# ProtoBoard.net
KiCad netlist of a schematic drawn in EAGLE
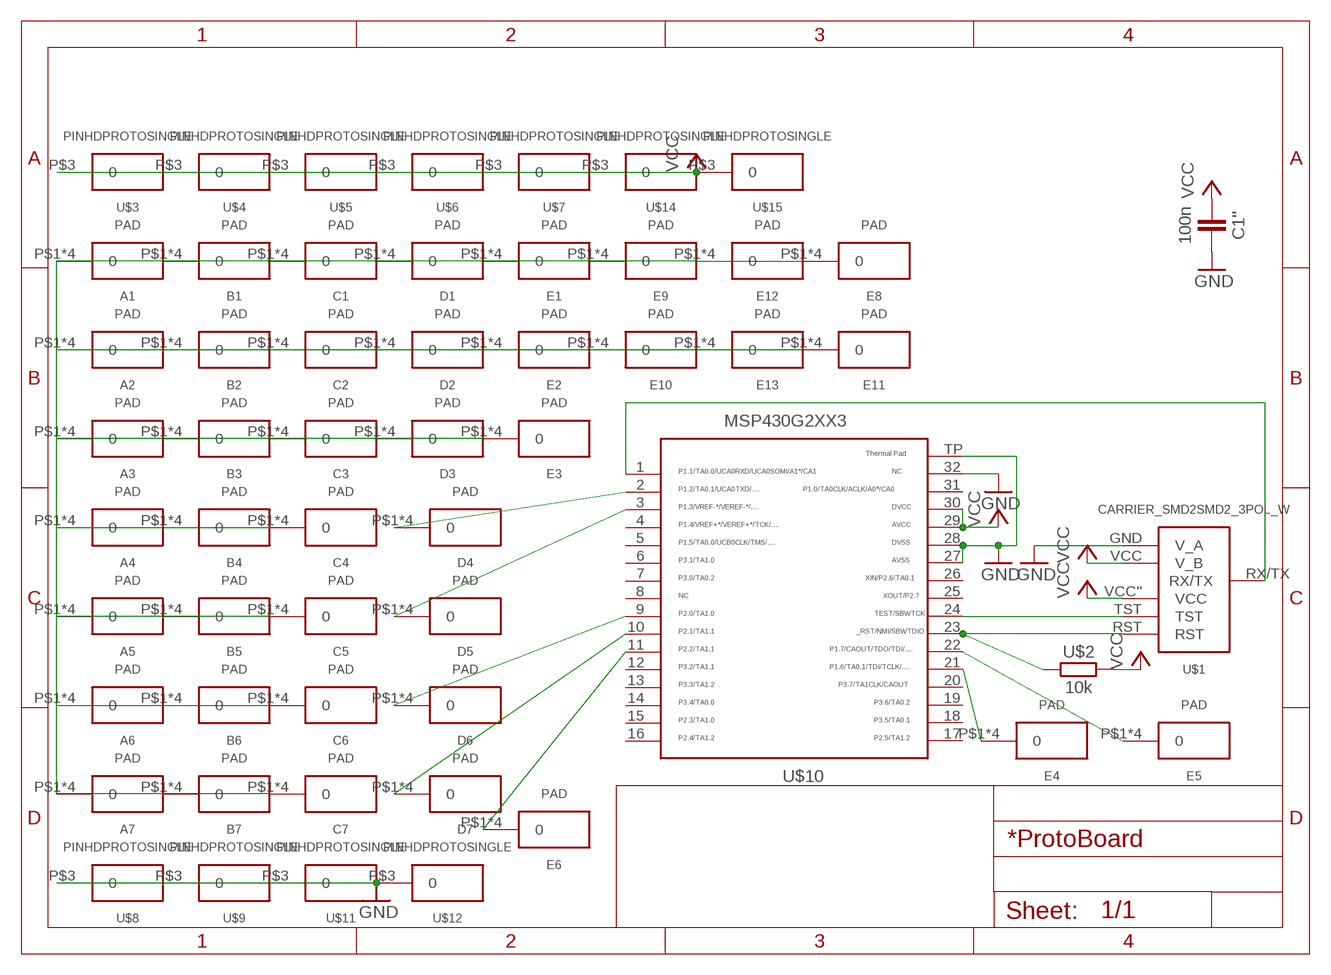
[diagram p0: schematic, sheet 1]

(export (version "E")
  (design (tool "Eeschema 10.0.6"))
  (components
    (comp (ref "A1")
      (value "PAD")
      (footprint "eagle-import:PROTPAD")
      (libsource (lib "eagle-import") (part "PINHDPROTOTYPING"))
    )
    (comp (ref "A2")
      (value "PAD")
      (footprint "eagle-import:PROTPAD")
      (libsource (lib "eagle-import") (part "PINHDPROTOTYPING"))
    )
    (comp (ref "A3")
      (value "PAD")
      (footprint "eagle-import:PROTPAD")
      (libsource (lib "eagle-import") (part "PINHDPROTOTYPING"))
    )
    (comp (ref "A4")
      (value "PAD")
      (footprint "eagle-import:PROTPAD")
      (libsource (lib "eagle-import") (part "PINHDPROTOTYPING"))
    )
    (comp (ref "A5")
      (value "PAD")
      (footprint "eagle-import:PROTPAD")
      (libsource (lib "eagle-import") (part "PINHDPROTOTYPING"))
    )
    (comp (ref "A6")
      (value "PAD")
      (footprint "eagle-import:PROTPAD")
      (libsource (lib "eagle-import") (part "PINHDPROTOTYPING"))
    )
    (comp (ref "A7")
      (value "PAD")
      (footprint "eagle-import:PROTPAD")
      (libsource (lib "eagle-import") (part "PINHDPROTOTYPING"))
    )
    (comp (ref "B1")
      (value "PAD")
      (footprint "eagle-import:PROTPAD")
      (libsource (lib "eagle-import") (part "PINHDPROTOTYPING"))
    )
    (comp (ref "B2")
      (value "PAD")
      (footprint "eagle-import:PROTPAD")
      (libsource (lib "eagle-import") (part "PINHDPROTOTYPING"))
    )
    (comp (ref "B3")
      (value "PAD")
      (footprint "eagle-import:PROTPAD")
      (libsource (lib "eagle-import") (part "PINHDPROTOTYPING"))
    )
    (comp (ref "B4")
      (value "PAD")
      (footprint "eagle-import:PROTPAD")
      (libsource (lib "eagle-import") (part "PINHDPROTOTYPING"))
    )
    (comp (ref "B5")
      (value "PAD")
      (footprint "eagle-import:PROTPAD")
      (libsource (lib "eagle-import") (part "PINHDPROTOTYPING"))
    )
    (comp (ref "B6")
      (value "PAD")
      (footprint "eagle-import:PROTPAD")
      (libsource (lib "eagle-import") (part "PINHDPROTOTYPING"))
    )
    (comp (ref "B7")
      (value "PAD")
      (footprint "eagle-import:PROTPAD")
      (libsource (lib "eagle-import") (part "PINHDPROTOTYPING"))
    )
    (comp (ref "C1")
      (value "PAD")
      (footprint "eagle-import:PROTPAD")
      (libsource (lib "eagle-import") (part "PINHDPROTOTYPING"))
    )
    (comp (ref "C1''")
      (value "100n")
      (footprint "eagle-import:603")
      (libsource (lib "eagle-import") (part "CAPACITOR"))
    )
    (comp (ref "C2")
      (value "PAD")
      (footprint "eagle-import:PROTPAD")
      (libsource (lib "eagle-import") (part "PINHDPROTOTYPING"))
    )
    (comp (ref "C3")
      (value "PAD")
      (footprint "eagle-import:PROTPAD")
      (libsource (lib "eagle-import") (part "PINHDPROTOTYPING"))
    )
    (comp (ref "C4")
      (value "PAD")
      (footprint "eagle-import:PROTPAD")
      (libsource (lib "eagle-import") (part "PINHDPROTOTYPING"))
    )
    (comp (ref "C5")
      (value "PAD")
      (footprint "eagle-import:PROTPAD")
      (libsource (lib "eagle-import") (part "PINHDPROTOTYPING"))
    )
    (comp (ref "C6")
      (value "PAD")
      (footprint "eagle-import:PROTPAD")
      (libsource (lib "eagle-import") (part "PINHDPROTOTYPING"))
    )
    (comp (ref "C7")
      (value "PAD")
      (footprint "eagle-import:PROTPAD")
      (libsource (lib "eagle-import") (part "PINHDPROTOTYPING"))
    )
    (comp (ref "D1")
      (value "PAD")
      (footprint "eagle-import:PROTPAD")
      (libsource (lib "eagle-import") (part "PINHDPROTOTYPING"))
    )
    (comp (ref "D2")
      (value "PAD")
      (footprint "eagle-import:PROTPAD")
      (libsource (lib "eagle-import") (part "PINHDPROTOTYPING"))
    )
    (comp (ref "D3")
      (value "PAD")
      (footprint "eagle-import:PROTPAD")
      (libsource (lib "eagle-import") (part "PINHDPROTOTYPING"))
    )
    (comp (ref "D4")
      (value "PAD")
      (footprint "eagle-import:PROTPAD")
      (libsource (lib "eagle-import") (part "PINHDPROTOTYPING"))
    )
    (comp (ref "D5")
      (value "PAD")
      (footprint "eagle-import:PROTPAD")
      (libsource (lib "eagle-import") (part "PINHDPROTOTYPING"))
    )
    (comp (ref "D6")
      (value "PAD")
      (footprint "eagle-import:PROTPAD")
      (libsource (lib "eagle-import") (part "PINHDPROTOTYPING"))
    )
    (comp (ref "D7")
      (value "PAD")
      (footprint "eagle-import:PROTPAD")
      (libsource (lib "eagle-import") (part "PINHDPROTOTYPING"))
    )
    (comp (ref "E1")
      (value "PAD")
      (footprint "eagle-import:PROTPAD")
      (libsource (lib "eagle-import") (part "PINHDPROTOTYPING"))
    )
    (comp (ref "E2")
      (value "PAD")
      (footprint "eagle-import:PROTPAD")
      (libsource (lib "eagle-import") (part "PINHDPROTOTYPING"))
    )
    (comp (ref "E3")
      (value "PAD")
      (footprint "eagle-import:PROTPAD")
      (libsource (lib "eagle-import") (part "PINHDPROTOTYPING"))
    )
    (comp (ref "E4")
      (value "PAD")
      (footprint "eagle-import:PROTPAD")
      (libsource (lib "eagle-import") (part "PINHDPROTOTYPING"))
    )
    (comp (ref "E5")
      (value "PAD")
      (footprint "eagle-import:PROTPAD")
      (libsource (lib "eagle-import") (part "PINHDPROTOTYPING"))
    )
    (comp (ref "E6")
      (value "PAD")
      (footprint "eagle-import:PROTPAD")
      (libsource (lib "eagle-import") (part "PINHDPROTOTYPING"))
    )
    (comp (ref "E8")
      (value "PAD")
      (footprint "eagle-import:PROTPAD")
      (libsource (lib "eagle-import") (part "PINHDPROTOTYPING"))
    )
    (comp (ref "E9")
      (value "PAD")
      (footprint "eagle-import:PROTPAD")
      (libsource (lib "eagle-import") (part "PINHDPROTOTYPING"))
    )
    (comp (ref "E10")
      (value "PAD")
      (footprint "eagle-import:PROTPAD")
      (libsource (lib "eagle-import") (part "PINHDPROTOTYPING"))
    )
    (comp (ref "E11")
      (value "PAD")
      (footprint "eagle-import:PROTPAD")
      (libsource (lib "eagle-import") (part "PINHDPROTOTYPING"))
    )
    (comp (ref "E12")
      (value "PAD")
      (footprint "eagle-import:PROTPAD")
      (libsource (lib "eagle-import") (part "PINHDPROTOTYPING"))
    )
    (comp (ref "E13")
      (value "PAD")
      (footprint "eagle-import:PROTPAD")
      (libsource (lib "eagle-import") (part "PINHDPROTOTYPING"))
    )
    (comp (ref "U$1")
      (value "CARRIER_SMD2SMD2_3POL_W")
      (footprint "eagle-import:CARRIER_SMD2_WIDE_3POL")
      (libsource (lib "eagle-import") (part "CARRIER_SMD2SMD2_3POL_W"))
    )
    (comp (ref "U$2")
      (value "10k")
      (footprint "eagle-import:603")
      (libsource (lib "eagle-import") (part "RESISTOR0603"))
    )
    (comp (ref "U$3")
      (value "PINHDPROTOSINGLE")
      (footprint "eagle-import:PROTOPADSINGLE")
      (libsource (lib "eagle-import") (part "PINHDPROTOSINGLE"))
    )
    (comp (ref "U$4")
      (value "PINHDPROTOSINGLE")
      (footprint "eagle-import:PROTOPADSINGLE")
      (libsource (lib "eagle-import") (part "PINHDPROTOSINGLE"))
    )
    (comp (ref "U$5")
      (value "PINHDPROTOSINGLE")
      (footprint "eagle-import:PROTOPADSINGLE")
      (libsource (lib "eagle-import") (part "PINHDPROTOSINGLE"))
    )
    (comp (ref "U$6")
      (value "PINHDPROTOSINGLE")
      (footprint "eagle-import:PROTOPADSINGLE")
      (libsource (lib "eagle-import") (part "PINHDPROTOSINGLE"))
    )
    (comp (ref "U$7")
      (value "PINHDPROTOSINGLE")
      (footprint "eagle-import:PROTOPADSINGLE")
      (libsource (lib "eagle-import") (part "PINHDPROTOSINGLE"))
    )
    (comp (ref "U$8")
      (value "PINHDPROTOSINGLE")
      (footprint "eagle-import:PROTOPADSINGLE")
      (libsource (lib "eagle-import") (part "PINHDPROTOSINGLE"))
    )
    (comp (ref "U$9")
      (value "PINHDPROTOSINGLE")
      (footprint "eagle-import:PROTOPADSINGLE")
      (libsource (lib "eagle-import") (part "PINHDPROTOSINGLE"))
    )
    (comp (ref "U$10")
      (value "MSP430G2553")
      (footprint "eagle-import:QFN32")
      (libsource (lib "eagle-import") (part "MSP430G2553"))
    )
    (comp (ref "U$11")
      (value "PINHDPROTOSINGLE")
      (footprint "eagle-import:PROTOPADSINGLE")
      (libsource (lib "eagle-import") (part "PINHDPROTOSINGLE"))
    )
    (comp (ref "U$12")
      (value "PINHDPROTOSINGLE")
      (footprint "eagle-import:PROTOPADSINGLE")
      (libsource (lib "eagle-import") (part "PINHDPROTOSINGLE"))
    )
    (comp (ref "U$14")
      (value "PINHDPROTOSINGLE")
      (footprint "eagle-import:PROTOPADSINGLE")
      (libsource (lib "eagle-import") (part "PINHDPROTOSINGLE"))
    )
    (comp (ref "U$15")
      (value "PINHDPROTOSINGLE")
      (footprint "eagle-import:PROTOPADSINGLE")
      (libsource (lib "eagle-import") (part "PINHDPROTOSINGLE"))
    )
  )
  (nets
    (net (code "1") (name "GND") (class "Default")
      (node (ref "C1''") (pin "2") (pinfunction "2_2") (pintype "passive"))
      (node (ref "U$1") (pin "GND") (pinfunction "V_A_GND") (pintype "bidirectional"))
      (node (ref "U$10") (pin "27") (pinfunction "27_27") (pintype "bidirectional"))
      (node (ref "U$10") (pin "28") (pinfunction "28_28") (pintype "bidirectional"))
      (node (ref "U$10") (pin "32") (pinfunction "32_32") (pintype "bidirectional"))
      (node (ref "U$10") (pin "TP") (pinfunction "TP_TP") (pintype "bidirectional"))
      (node (ref "U$11") (pin "P$3") (pinfunction "0_P$3") (pintype "bidirectional"))
      (node (ref "U$12") (pin "P$3") (pinfunction "0_P$3") (pintype "bidirectional"))
      (node (ref "U$8") (pin "P$3") (pinfunction "0_P$3") (pintype "bidirectional"))
      (node (ref "U$9") (pin "P$3") (pinfunction "0_P$3") (pintype "bidirectional"))
    )
    (net (code "2") (name "Net-(A1-0-PadP$1)") (class "Default")
      (node (ref "A1") (pin "P$1") (pinfunction "0_P$1") (pintype "bidirectional"))
      (node (ref "A1") (pin "P$2") (pinfunction "0_P$2") (pintype "bidirectional"))
      (node (ref "A1") (pin "P$3") (pinfunction "0_P$3") (pintype "bidirectional"))
      (node (ref "A1") (pin "P$4") (pinfunction "0_P$4") (pintype "bidirectional"))
      (node (ref "A2") (pin "P$1") (pinfunction "0_P$1") (pintype "bidirectional"))
      (node (ref "A2") (pin "P$2") (pinfunction "0_P$2") (pintype "bidirectional"))
      (node (ref "A2") (pin "P$3") (pinfunction "0_P$3") (pintype "bidirectional"))
      (node (ref "A2") (pin "P$4") (pinfunction "0_P$4") (pintype "bidirectional"))
      (node (ref "A3") (pin "P$1") (pinfunction "0_P$1") (pintype "bidirectional"))
      (node (ref "A3") (pin "P$2") (pinfunction "0_P$2") (pintype "bidirectional"))
      (node (ref "A3") (pin "P$3") (pinfunction "0_P$3") (pintype "bidirectional"))
      (node (ref "A3") (pin "P$4") (pinfunction "0_P$4") (pintype "bidirectional"))
      (node (ref "A4") (pin "P$1") (pinfunction "0_P$1") (pintype "bidirectional"))
      (node (ref "A4") (pin "P$2") (pinfunction "0_P$2") (pintype "bidirectional"))
      (node (ref "A4") (pin "P$3") (pinfunction "0_P$3") (pintype "bidirectional"))
      (node (ref "A4") (pin "P$4") (pinfunction "0_P$4") (pintype "bidirectional"))
      (node (ref "A5") (pin "P$1") (pinfunction "0_P$1") (pintype "bidirectional"))
      (node (ref "A5") (pin "P$2") (pinfunction "0_P$2") (pintype "bidirectional"))
      (node (ref "A5") (pin "P$3") (pinfunction "0_P$3") (pintype "bidirectional"))
      (node (ref "A5") (pin "P$4") (pinfunction "0_P$4") (pintype "bidirectional"))
      (node (ref "A6") (pin "P$1") (pinfunction "0_P$1") (pintype "bidirectional"))
      (node (ref "A6") (pin "P$2") (pinfunction "0_P$2") (pintype "bidirectional"))
      (node (ref "A6") (pin "P$3") (pinfunction "0_P$3") (pintype "bidirectional"))
      (node (ref "A6") (pin "P$4") (pinfunction "0_P$4") (pintype "bidirectional"))
      (node (ref "A7") (pin "P$1") (pinfunction "0_P$1") (pintype "bidirectional"))
      (node (ref "A7") (pin "P$2") (pinfunction "0_P$2") (pintype "bidirectional"))
      (node (ref "A7") (pin "P$3") (pinfunction "0_P$3") (pintype "bidirectional"))
      (node (ref "A7") (pin "P$4") (pinfunction "0_P$4") (pintype "bidirectional"))
      (node (ref "B1") (pin "P$1") (pinfunction "0_P$1") (pintype "bidirectional"))
      (node (ref "B1") (pin "P$2") (pinfunction "0_P$2") (pintype "bidirectional"))
      (node (ref "B1") (pin "P$3") (pinfunction "0_P$3") (pintype "bidirectional"))
      (node (ref "B1") (pin "P$4") (pinfunction "0_P$4") (pintype "bidirectional"))
      (node (ref "B2") (pin "P$1") (pinfunction "0_P$1") (pintype "bidirectional"))
      (node (ref "B2") (pin "P$2") (pinfunction "0_P$2") (pintype "bidirectional"))
      (node (ref "B2") (pin "P$3") (pinfunction "0_P$3") (pintype "bidirectional"))
      (node (ref "B2") (pin "P$4") (pinfunction "0_P$4") (pintype "bidirectional"))
      (node (ref "B3") (pin "P$1") (pinfunction "0_P$1") (pintype "bidirectional"))
      (node (ref "B3") (pin "P$2") (pinfunction "0_P$2") (pintype "bidirectional"))
      (node (ref "B3") (pin "P$3") (pinfunction "0_P$3") (pintype "bidirectional"))
      (node (ref "B3") (pin "P$4") (pinfunction "0_P$4") (pintype "bidirectional"))
      (node (ref "B4") (pin "P$1") (pinfunction "0_P$1") (pintype "bidirectional"))
      (node (ref "B4") (pin "P$2") (pinfunction "0_P$2") (pintype "bidirectional"))
      (node (ref "B4") (pin "P$3") (pinfunction "0_P$3") (pintype "bidirectional"))
      (node (ref "B4") (pin "P$4") (pinfunction "0_P$4") (pintype "bidirectional"))
      (node (ref "B5") (pin "P$1") (pinfunction "0_P$1") (pintype "bidirectional"))
      (node (ref "B5") (pin "P$2") (pinfunction "0_P$2") (pintype "bidirectional"))
      (node (ref "B5") (pin "P$3") (pinfunction "0_P$3") (pintype "bidirectional"))
      (node (ref "B5") (pin "P$4") (pinfunction "0_P$4") (pintype "bidirectional"))
      (node (ref "B6") (pin "P$1") (pinfunction "0_P$1") (pintype "bidirectional"))
      (node (ref "B6") (pin "P$2") (pinfunction "0_P$2") (pintype "bidirectional"))
      (node (ref "B6") (pin "P$3") (pinfunction "0_P$3") (pintype "bidirectional"))
      (node (ref "B6") (pin "P$4") (pinfunction "0_P$4") (pintype "bidirectional"))
      (node (ref "B7") (pin "P$1") (pinfunction "0_P$1") (pintype "bidirectional"))
      (node (ref "B7") (pin "P$2") (pinfunction "0_P$2") (pintype "bidirectional"))
      (node (ref "B7") (pin "P$3") (pinfunction "0_P$3") (pintype "bidirectional"))
      (node (ref "B7") (pin "P$4") (pinfunction "0_P$4") (pintype "bidirectional"))
      (node (ref "C1") (pin "P$1") (pinfunction "0_P$1") (pintype "bidirectional"))
      (node (ref "C1") (pin "P$2") (pinfunction "0_P$2") (pintype "bidirectional"))
      (node (ref "C1") (pin "P$3") (pinfunction "0_P$3") (pintype "bidirectional"))
      (node (ref "C1") (pin "P$4") (pinfunction "0_P$4") (pintype "bidirectional"))
      (node (ref "C2") (pin "P$1") (pinfunction "0_P$1") (pintype "bidirectional"))
      (node (ref "C2") (pin "P$2") (pinfunction "0_P$2") (pintype "bidirectional"))
      (node (ref "C2") (pin "P$3") (pinfunction "0_P$3") (pintype "bidirectional"))
      (node (ref "C2") (pin "P$4") (pinfunction "0_P$4") (pintype "bidirectional"))
      (node (ref "C3") (pin "P$1") (pinfunction "0_P$1") (pintype "bidirectional"))
      (node (ref "C3") (pin "P$2") (pinfunction "0_P$2") (pintype "bidirectional"))
      (node (ref "C3") (pin "P$3") (pinfunction "0_P$3") (pintype "bidirectional"))
      (node (ref "C3") (pin "P$4") (pinfunction "0_P$4") (pintype "bidirectional"))
      (node (ref "C4") (pin "P$1") (pinfunction "0_P$1") (pintype "bidirectional"))
      (node (ref "C4") (pin "P$2") (pinfunction "0_P$2") (pintype "bidirectional"))
      (node (ref "C4") (pin "P$3") (pinfunction "0_P$3") (pintype "bidirectional"))
      (node (ref "C4") (pin "P$4") (pinfunction "0_P$4") (pintype "bidirectional"))
      (node (ref "C5") (pin "P$1") (pinfunction "0_P$1") (pintype "bidirectional"))
      (node (ref "C5") (pin "P$2") (pinfunction "0_P$2") (pintype "bidirectional"))
      (node (ref "C5") (pin "P$3") (pinfunction "0_P$3") (pintype "bidirectional"))
      (node (ref "C5") (pin "P$4") (pinfunction "0_P$4") (pintype "bidirectional"))
      (node (ref "C6") (pin "P$1") (pinfunction "0_P$1") (pintype "bidirectional"))
      (node (ref "C6") (pin "P$2") (pinfunction "0_P$2") (pintype "bidirectional"))
      (node (ref "C6") (pin "P$3") (pinfunction "0_P$3") (pintype "bidirectional"))
      (node (ref "C6") (pin "P$4") (pinfunction "0_P$4") (pintype "bidirectional"))
      (node (ref "C7") (pin "P$1") (pinfunction "0_P$1") (pintype "bidirectional"))
      (node (ref "C7") (pin "P$2") (pinfunction "0_P$2") (pintype "bidirectional"))
      (node (ref "C7") (pin "P$3") (pinfunction "0_P$3") (pintype "bidirectional"))
      (node (ref "C7") (pin "P$4") (pinfunction "0_P$4") (pintype "bidirectional"))
      (node (ref "D1") (pin "P$1") (pinfunction "0_P$1") (pintype "bidirectional"))
      (node (ref "D1") (pin "P$2") (pinfunction "0_P$2") (pintype "bidirectional"))
      (node (ref "D1") (pin "P$3") (pinfunction "0_P$3") (pintype "bidirectional"))
      (node (ref "D1") (pin "P$4") (pinfunction "0_P$4") (pintype "bidirectional"))
      (node (ref "D2") (pin "P$1") (pinfunction "0_P$1") (pintype "bidirectional"))
      (node (ref "D2") (pin "P$2") (pinfunction "0_P$2") (pintype "bidirectional"))
      (node (ref "D2") (pin "P$3") (pinfunction "0_P$3") (pintype "bidirectional"))
      (node (ref "D2") (pin "P$4") (pinfunction "0_P$4") (pintype "bidirectional"))
      (node (ref "D3") (pin "P$1") (pinfunction "0_P$1") (pintype "bidirectional"))
      (node (ref "D3") (pin "P$2") (pinfunction "0_P$2") (pintype "bidirectional"))
      (node (ref "D3") (pin "P$3") (pinfunction "0_P$3") (pintype "bidirectional"))
      (node (ref "D3") (pin "P$4") (pinfunction "0_P$4") (pintype "bidirectional"))
      (node (ref "E1") (pin "P$1") (pinfunction "0_P$1") (pintype "bidirectional"))
      (node (ref "E1") (pin "P$2") (pinfunction "0_P$2") (pintype "bidirectional"))
      (node (ref "E1") (pin "P$3") (pinfunction "0_P$3") (pintype "bidirectional"))
      (node (ref "E1") (pin "P$4") (pinfunction "0_P$4") (pintype "bidirectional"))
      (node (ref "E10") (pin "P$1") (pinfunction "0_P$1") (pintype "bidirectional"))
      (node (ref "E10") (pin "P$2") (pinfunction "0_P$2") (pintype "bidirectional"))
      (node (ref "E10") (pin "P$3") (pinfunction "0_P$3") (pintype "bidirectional"))
      (node (ref "E10") (pin "P$4") (pinfunction "0_P$4") (pintype "bidirectional"))
      (node (ref "E11") (pin "P$1") (pinfunction "0_P$1") (pintype "bidirectional"))
      (node (ref "E11") (pin "P$2") (pinfunction "0_P$2") (pintype "bidirectional"))
      (node (ref "E11") (pin "P$3") (pinfunction "0_P$3") (pintype "bidirectional"))
      (node (ref "E11") (pin "P$4") (pinfunction "0_P$4") (pintype "bidirectional"))
      (node (ref "E12") (pin "P$1") (pinfunction "0_P$1") (pintype "bidirectional"))
      (node (ref "E12") (pin "P$2") (pinfunction "0_P$2") (pintype "bidirectional"))
      (node (ref "E12") (pin "P$3") (pinfunction "0_P$3") (pintype "bidirectional"))
      (node (ref "E12") (pin "P$4") (pinfunction "0_P$4") (pintype "bidirectional"))
      (node (ref "E13") (pin "P$1") (pinfunction "0_P$1") (pintype "bidirectional"))
      (node (ref "E13") (pin "P$2") (pinfunction "0_P$2") (pintype "bidirectional"))
      (node (ref "E13") (pin "P$3") (pinfunction "0_P$3") (pintype "bidirectional"))
      (node (ref "E13") (pin "P$4") (pinfunction "0_P$4") (pintype "bidirectional"))
      (node (ref "E2") (pin "P$1") (pinfunction "0_P$1") (pintype "bidirectional"))
      (node (ref "E2") (pin "P$2") (pinfunction "0_P$2") (pintype "bidirectional"))
      (node (ref "E2") (pin "P$3") (pinfunction "0_P$3") (pintype "bidirectional"))
      (node (ref "E2") (pin "P$4") (pinfunction "0_P$4") (pintype "bidirectional"))
      (node (ref "E3") (pin "P$1") (pinfunction "0_P$1") (pintype "bidirectional"))
      (node (ref "E3") (pin "P$2") (pinfunction "0_P$2") (pintype "bidirectional"))
      (node (ref "E3") (pin "P$3") (pinfunction "0_P$3") (pintype "bidirectional"))
      (node (ref "E3") (pin "P$4") (pinfunction "0_P$4") (pintype "bidirectional"))
      (node (ref "E8") (pin "P$1") (pinfunction "0_P$1") (pintype "bidirectional"))
      (node (ref "E8") (pin "P$2") (pinfunction "0_P$2") (pintype "bidirectional"))
      (node (ref "E8") (pin "P$3") (pinfunction "0_P$3") (pintype "bidirectional"))
      (node (ref "E8") (pin "P$4") (pinfunction "0_P$4") (pintype "bidirectional"))
      (node (ref "E9") (pin "P$1") (pinfunction "0_P$1") (pintype "bidirectional"))
      (node (ref "E9") (pin "P$2") (pinfunction "0_P$2") (pintype "bidirectional"))
      (node (ref "E9") (pin "P$3") (pinfunction "0_P$3") (pintype "bidirectional"))
      (node (ref "E9") (pin "P$4") (pinfunction "0_P$4") (pintype "bidirectional"))
    )
    (net (code "3") (name "Net-(D4-0-PadP$1)") (class "Default")
      (node (ref "D4") (pin "P$1") (pinfunction "0_P$1") (pintype "bidirectional"))
      (node (ref "D4") (pin "P$2") (pinfunction "0_P$2") (pintype "bidirectional"))
      (node (ref "D4") (pin "P$3") (pinfunction "0_P$3") (pintype "bidirectional"))
      (node (ref "D4") (pin "P$4") (pinfunction "0_P$4") (pintype "bidirectional"))
      (node (ref "U$10") (pin "2") (pinfunction "2_2") (pintype "bidirectional"))
    )
    (net (code "4") (name "Net-(D5-0-PadP$1)") (class "Default")
      (node (ref "D5") (pin "P$1") (pinfunction "0_P$1") (pintype "bidirectional"))
      (node (ref "D5") (pin "P$2") (pinfunction "0_P$2") (pintype "bidirectional"))
      (node (ref "D5") (pin "P$3") (pinfunction "0_P$3") (pintype "bidirectional"))
      (node (ref "D5") (pin "P$4") (pinfunction "0_P$4") (pintype "bidirectional"))
      (node (ref "U$10") (pin "3") (pinfunction "3_3") (pintype "bidirectional"))
    )
    (net (code "5") (name "Net-(D6-0-PadP$1)") (class "Default")
      (node (ref "D6") (pin "P$1") (pinfunction "0_P$1") (pintype "bidirectional"))
      (node (ref "D6") (pin "P$2") (pinfunction "0_P$2") (pintype "bidirectional"))
      (node (ref "D6") (pin "P$3") (pinfunction "0_P$3") (pintype "bidirectional"))
      (node (ref "D6") (pin "P$4") (pinfunction "0_P$4") (pintype "bidirectional"))
      (node (ref "U$10") (pin "9") (pinfunction "9_9") (pintype "bidirectional"))
    )
    (net (code "6") (name "Net-(D7-0-PadP$1)") (class "Default")
      (node (ref "D7") (pin "P$1") (pinfunction "0_P$1") (pintype "bidirectional"))
      (node (ref "D7") (pin "P$2") (pinfunction "0_P$2") (pintype "bidirectional"))
      (node (ref "D7") (pin "P$3") (pinfunction "0_P$3") (pintype "bidirectional"))
      (node (ref "D7") (pin "P$4") (pinfunction "0_P$4") (pintype "bidirectional"))
      (node (ref "U$10") (pin "10") (pinfunction "10_10") (pintype "bidirectional"))
    )
    (net (code "7") (name "Net-(E4-0-PadP$1)") (class "Default")
      (node (ref "E4") (pin "P$1") (pinfunction "0_P$1") (pintype "bidirectional"))
      (node (ref "E4") (pin "P$2") (pinfunction "0_P$2") (pintype "bidirectional"))
      (node (ref "E4") (pin "P$3") (pinfunction "0_P$3") (pintype "bidirectional"))
      (node (ref "E4") (pin "P$4") (pinfunction "0_P$4") (pintype "bidirectional"))
      (node (ref "U$10") (pin "21") (pinfunction "21_21") (pintype "bidirectional"))
    )
    (net (code "8") (name "Net-(E5-0-PadP$1)") (class "Default")
      (node (ref "E5") (pin "P$1") (pinfunction "0_P$1") (pintype "bidirectional"))
      (node (ref "E5") (pin "P$2") (pinfunction "0_P$2") (pintype "bidirectional"))
      (node (ref "E5") (pin "P$3") (pinfunction "0_P$3") (pintype "bidirectional"))
      (node (ref "E5") (pin "P$4") (pinfunction "0_P$4") (pintype "bidirectional"))
      (node (ref "U$10") (pin "22") (pinfunction "22_22") (pintype "bidirectional"))
    )
    (net (code "9") (name "Net-(E6-0-PadP$1)") (class "Default")
      (node (ref "E6") (pin "P$1") (pinfunction "0_P$1") (pintype "bidirectional"))
      (node (ref "E6") (pin "P$2") (pinfunction "0_P$2") (pintype "bidirectional"))
      (node (ref "E6") (pin "P$3") (pinfunction "0_P$3") (pintype "bidirectional"))
      (node (ref "E6") (pin "P$4") (pinfunction "0_P$4") (pintype "bidirectional"))
      (node (ref "U$10") (pin "11") (pinfunction "11_11") (pintype "bidirectional"))
    )
    (net (code "10") (name "Net-(U$1-PadRST)") (class "Default")
      (node (ref "U$1") (pin "RST") (pinfunction "RST_RST") (pintype "bidirectional"))
      (node (ref "U$10") (pin "23") (pinfunction "23_23") (pintype "bidirectional"))
      (node (ref "U$2") (pin "1") (pinfunction "1_1") (pintype "passive"))
    )
    (net (code "11") (name "Net-(U$1-PadRX{slash}TX)") (class "Default")
      (node (ref "U$1") (pin "RX/TX") (pinfunction "RX/TX_RX/TX") (pintype "bidirectional"))
      (node (ref "U$10") (pin "1") (pinfunction "1_1") (pintype "bidirectional"))
    )
    (net (code "12") (name "Net-(U$1-PadTST)") (class "Default")
      (node (ref "U$1") (pin "TST") (pinfunction "TST_TST") (pintype "bidirectional"))
      (node (ref "U$10") (pin "24") (pinfunction "24_24") (pintype "bidirectional"))
    )
    (net (code "13") (name "VCC") (class "Default")
      (node (ref "C1''") (pin "1") (pinfunction "1_1") (pintype "passive"))
      (node (ref "U$1") (pin "VCC") (pinfunction "V_B_VCC") (pintype "bidirectional"))
      (node (ref "U$1") (pin "VCC''") (pinfunction "VCC_VCC''") (pintype "bidirectional"))
      (node (ref "U$10") (pin "29") (pinfunction "29_29") (pintype "bidirectional"))
      (node (ref "U$10") (pin "30") (pinfunction "30_30") (pintype "bidirectional"))
      (node (ref "U$14") (pin "P$3") (pinfunction "0_P$3") (pintype "bidirectional"))
      (node (ref "U$15") (pin "P$3") (pinfunction "0_P$3") (pintype "bidirectional"))
      (node (ref "U$2") (pin "2") (pinfunction "2_2") (pintype "passive"))
      (node (ref "U$3") (pin "P$3") (pinfunction "0_P$3") (pintype "bidirectional"))
      (node (ref "U$4") (pin "P$3") (pinfunction "0_P$3") (pintype "bidirectional"))
      (node (ref "U$5") (pin "P$3") (pinfunction "0_P$3") (pintype "bidirectional"))
      (node (ref "U$6") (pin "P$3") (pinfunction "0_P$3") (pintype "bidirectional"))
      (node (ref "U$7") (pin "P$3") (pinfunction "0_P$3") (pintype "bidirectional"))
    )
    (net (code "14") (name "unconnected-(U$10-Pad4)") (class "Default")
      (node (ref "U$10") (pin "4") (pinfunction "4_4") (pintype "bidirectional"))
    )
    (net (code "15") (name "unconnected-(U$10-Pad5)") (class "Default")
      (node (ref "U$10") (pin "5") (pinfunction "5_5") (pintype "bidirectional"))
    )
    (net (code "16") (name "unconnected-(U$10-Pad6)") (class "Default")
      (node (ref "U$10") (pin "6") (pinfunction "6_6") (pintype "bidirectional"))
    )
    (net (code "17") (name "unconnected-(U$10-Pad7)") (class "Default")
      (node (ref "U$10") (pin "7") (pinfunction "7_7") (pintype "bidirectional"))
    )
    (net (code "18") (name "unconnected-(U$10-Pad8)") (class "Default")
      (node (ref "U$10") (pin "8") (pinfunction "8_8") (pintype "bidirectional"))
    )
    (net (code "19") (name "unconnected-(U$10-Pad12)") (class "Default")
      (node (ref "U$10") (pin "12") (pinfunction "12_12") (pintype "bidirectional"))
    )
    (net (code "20") (name "unconnected-(U$10-Pad13)") (class "Default")
      (node (ref "U$10") (pin "13") (pinfunction "13_13") (pintype "bidirectional"))
    )
    (net (code "21") (name "unconnected-(U$10-Pad14)") (class "Default")
      (node (ref "U$10") (pin "14") (pinfunction "14_14") (pintype "bidirectional"))
    )
    (net (code "22") (name "unconnected-(U$10-Pad15)") (class "Default")
      (node (ref "U$10") (pin "15") (pinfunction "15_15") (pintype "bidirectional"))
    )
    (net (code "23") (name "unconnected-(U$10-Pad16)") (class "Default")
      (node (ref "U$10") (pin "16") (pinfunction "16_16") (pintype "bidirectional"))
    )
    (net (code "24") (name "unconnected-(U$10-Pad17)") (class "Default")
      (node (ref "U$10") (pin "17") (pinfunction "17_17") (pintype "bidirectional"))
    )
    (net (code "25") (name "unconnected-(U$10-Pad18)") (class "Default")
      (node (ref "U$10") (pin "18") (pinfunction "18_18") (pintype "bidirectional"))
    )
    (net (code "26") (name "unconnected-(U$10-Pad19)") (class "Default")
      (node (ref "U$10") (pin "19") (pinfunction "19_19") (pintype "bidirectional"))
    )
    (net (code "27") (name "unconnected-(U$10-Pad20)") (class "Default")
      (node (ref "U$10") (pin "20") (pinfunction "20_20") (pintype "bidirectional"))
    )
    (net (code "28") (name "unconnected-(U$10-Pad25)") (class "Default")
      (node (ref "U$10") (pin "25") (pinfunction "25_25") (pintype "bidirectional"))
    )
    (net (code "29") (name "unconnected-(U$10-Pad26)") (class "Default")
      (node (ref "U$10") (pin "26") (pinfunction "26_26") (pintype "bidirectional"))
    )
    (net (code "30") (name "unconnected-(U$10-Pad31)") (class "Default")
      (node (ref "U$10") (pin "31") (pinfunction "31_31") (pintype "bidirectional"))
    )
  )
)
